# 20260908.net
KiCad netlist of a schematic drawn in Altium Designer
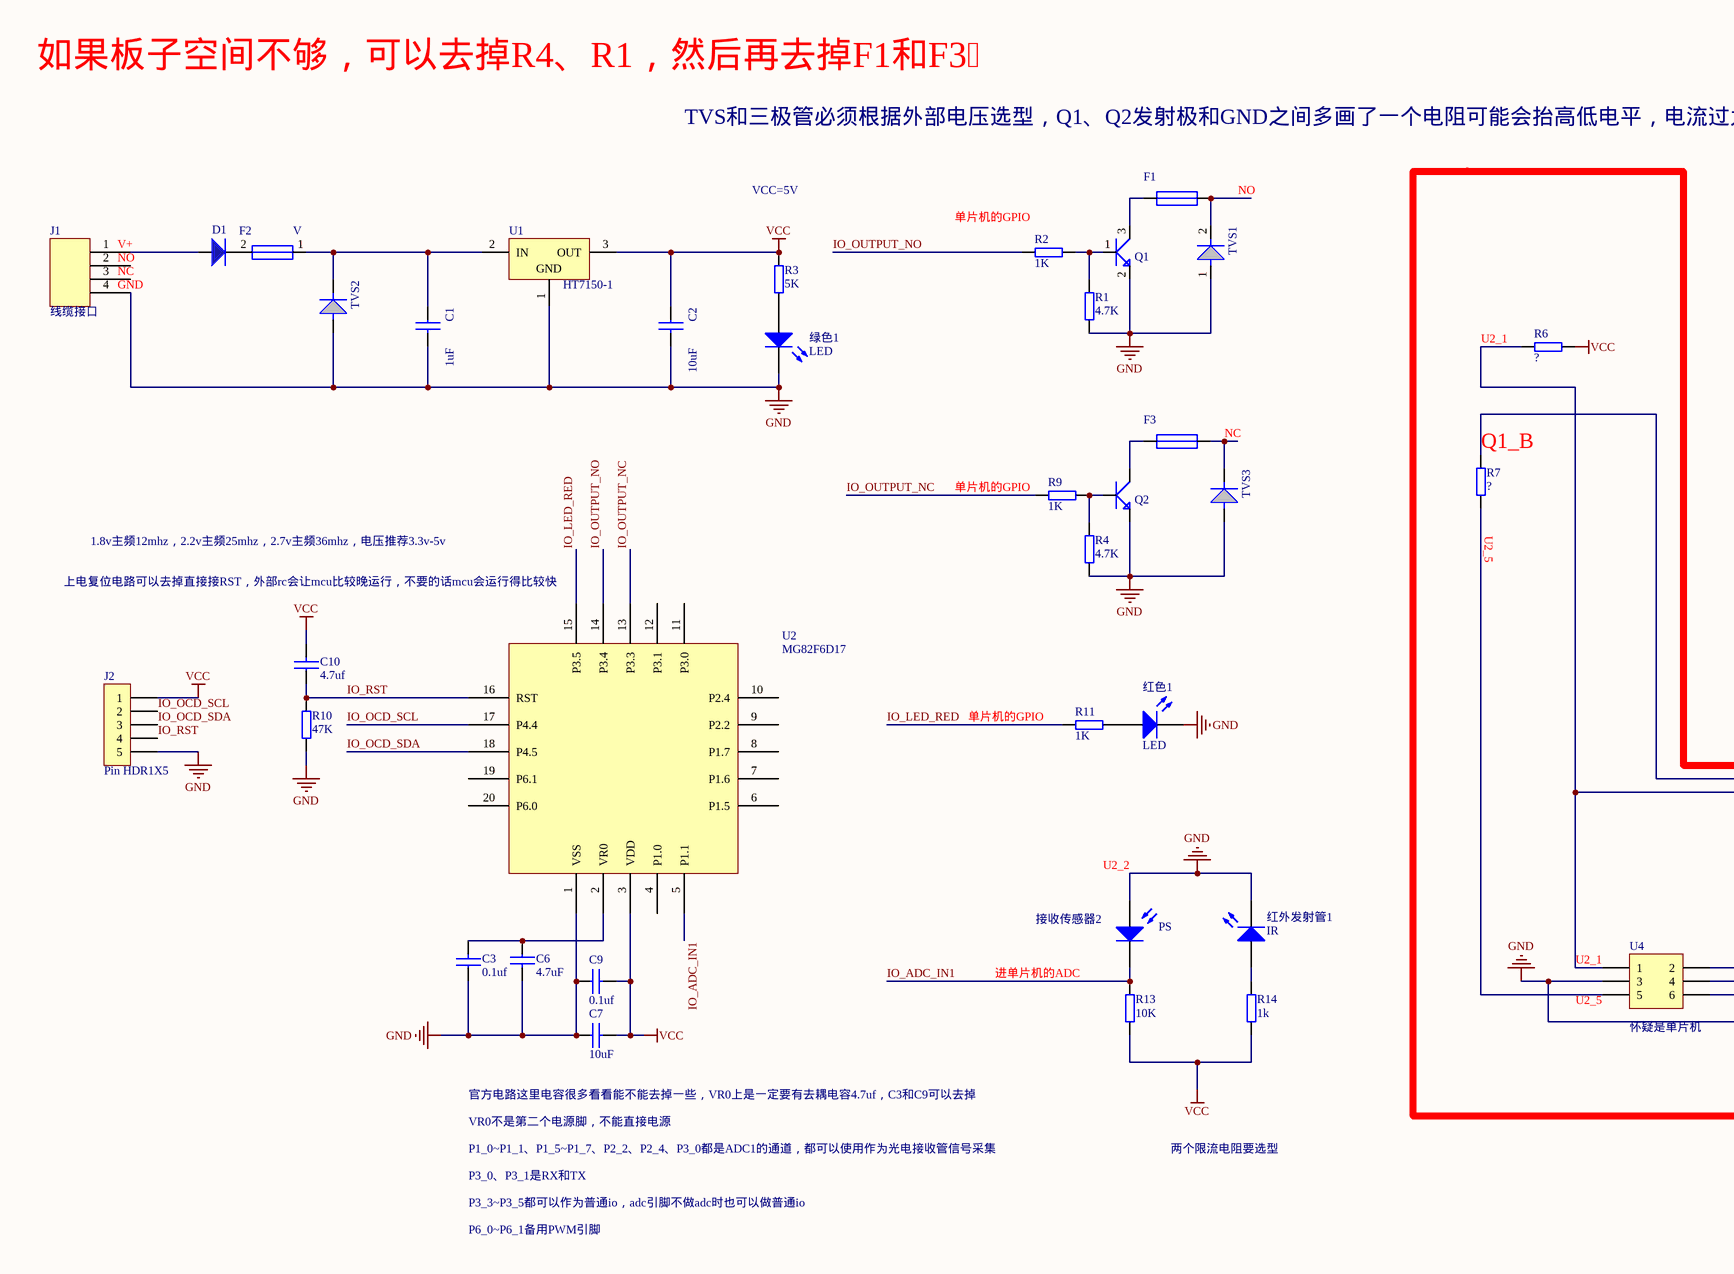
[diagram p0: 槽形开关原理图20260908.SchDoc, left]
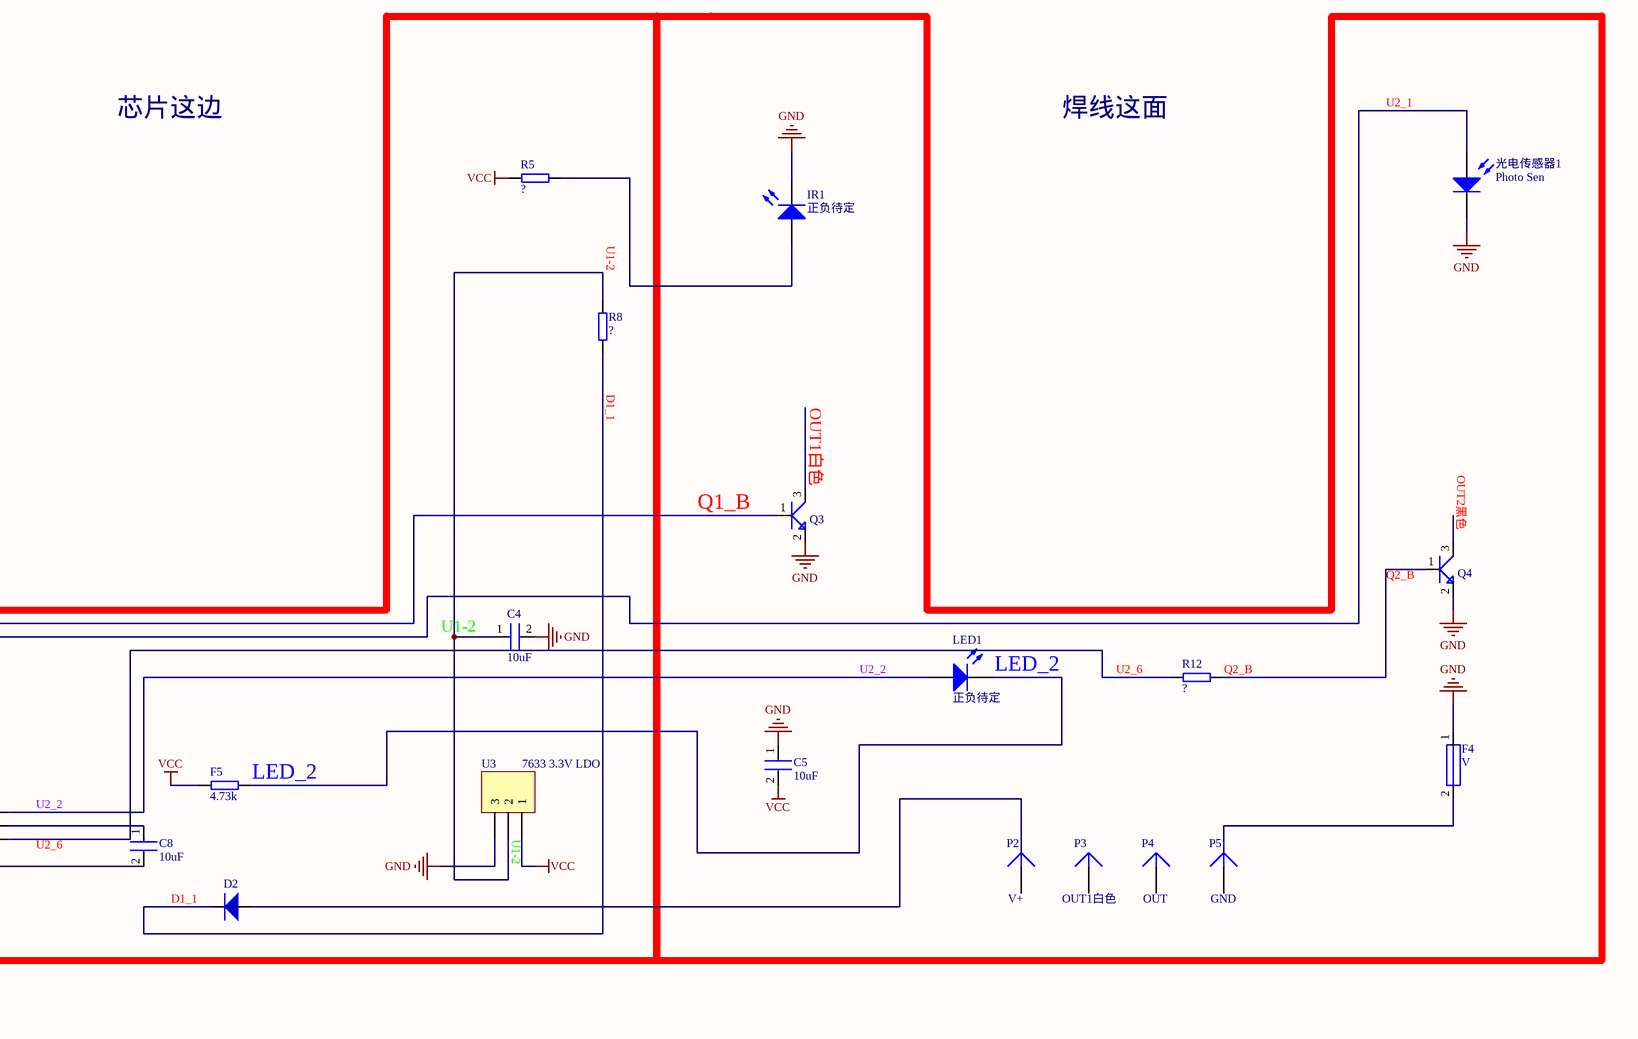
[diagram p1: 槽形开关原理图20260908.SchDoc, right]

(export (version "E")
  (design (tool "Eeschema 10.0.6"))
  (components
    (comp (ref "C1") (value "1uF") (footprint "1206") (libsource (lib "*") (part "CAP NP")))
    (comp (ref "C2") (value "10uF") (footprint "1206") (libsource (lib "*") (part "CAP NP")))
    (comp (ref "C3") (value "0.1uf") (footprint "1206") (libsource (lib "*") (part "CAP NP")))
    (comp (ref "C4") (value "10uF") (libsource (lib "*") (part "CAP")))
    (comp (ref "C5") (value "10uF") (libsource (lib "*") (part "CAP")))
    (comp (ref "C6") (value "4.7uF") (footprint "1206") (libsource (lib "*") (part "CAP NP")))
    (comp (ref "C7") (value "10uF") (footprint "1206") (libsource (lib "*") (part "CAP NP")))
    (comp (ref "C8") (value "10uF") (libsource (lib "*") (part "CAP")))
    (comp (ref "C9") (value "0.1uf") (footprint "1206") (libsource (lib "*") (part "CAP NP")))
    (comp (ref "C10") (value "4.7uf") (footprint "1206") (libsource (lib "*") (part "CAP NP")))
    (comp (ref "D1") (value "~") (libsource (lib "*") (part "D")))
    (comp (ref "D2") (value "~") (libsource (lib "*") (part "D")))
    (comp (ref "F1") (value "V") (footprint "0805") (libsource (lib "") (part "FUSE_0_2")))
    (comp (ref "F2") (value "V") (footprint "0805") (libsource (lib "*") (part "FUSE_0")))
    (comp (ref "F3") (value "~") (footprint "0805") (libsource (lib "") (part "FUSE_0_2")))
    (comp (ref "F4") (value "V") (footprint "0805") (libsource (lib "") (part "FUSE_0_1")))
    (comp (ref "F5") (value "4.73k") (libsource (lib "*") (part "RES")))
    (comp (ref "IR1")
      (value "正负待定")
      (footprint "LED-0")
      (description "Typical INFRARED GaAs LED")
      (fields (field (name "PUBLISHER") "Altium Limited"))
      (libsource (lib "Miscellaneous Devices") (part "LED0"))
    )
    (comp (ref "J1") (value "线缆接口") (footprint "SIP4") (libsource (lib "*") (part "4H")))
    (comp (ref "J2")
      (value "Pin HDR1X5")
      (footprint "Pin HDR1X5/2mm-W")
      (libsource (lib "排针") (part "Pin HDR1X5"))
    )
    (comp (ref "LED1")
      (value "正负待定")
      (footprint "LED-0")
      (description "Typical INFRARED GaAs LED")
      (fields (field (name "PUBLISHER") "Altium Limited"))
      (libsource (lib "Miscellaneous Devices") (part "LED0"))
    )
    (comp (ref "P2")
      (value "V+")
      (footprint "PIN1")
      (description "Plug")
      (fields (field (name "PUBLISHER") "Altium Limited"))
      (libsource (lib "Miscellaneous Connectors") (part "Plug"))
    )
    (comp (ref "P3")
      (value "OUT1白色")
      (footprint "PIN1")
      (description "Plug")
      (fields (field (name "PUBLISHER") "Altium Limited"))
      (libsource (lib "Miscellaneous Connectors") (part "Plug"))
    )
    (comp (ref "P4")
      (value "OUT")
      (footprint "PIN1")
      (description "Plug")
      (fields (field (name "PUBLISHER") "Altium Limited"))
      (libsource (lib "Miscellaneous Connectors") (part "Plug"))
    )
    (comp (ref "P5")
      (value "GND")
      (footprint "PIN1")
      (description "Plug")
      (fields (field (name "PUBLISHER") "Altium Limited"))
      (libsource (lib "Miscellaneous Connectors") (part "Plug"))
    )
    (comp (ref "Q1") (value "2SC4617TLR") (libsource (lib "*") (part "2SC4617")))
    (comp (ref "Q2") (value "2SC4617TLR") (libsource (lib "") (part "2SC4617_1")))
    (comp (ref "Q3") (value "2SC4617TLR") (libsource (lib "*") (part "2SC4617")))
    (comp (ref "Q4") (value "2SC4617TLR") (libsource (lib "*") (part "2SC4617")))
    (comp (ref "R1") (value "4.7K") (libsource (lib "*") (part "RES")))
    (comp (ref "R2") (value "1K") (libsource (lib "*") (part "RES")))
    (comp (ref "R3") (value "5K") (libsource (lib "*") (part "RES")))
    (comp (ref "R4") (value "4.7K") (libsource (lib "*") (part "RES")))
    (comp (ref "R5") (value "?") (libsource (lib "*") (part "RES")))
    (comp (ref "R6") (value "?") (libsource (lib "*") (part "RES")))
    (comp (ref "R7") (value "?") (libsource (lib "*") (part "RES")))
    (comp (ref "R8") (value "?") (libsource (lib "*") (part "RES")))
    (comp (ref "R9") (value "1K") (libsource (lib "*") (part "RES")))
    (comp (ref "R10") (value "47K") (libsource (lib "*") (part "RES")))
    (comp (ref "R11") (value "1K") (libsource (lib "*") (part "RES")))
    (comp (ref "R12") (value "?") (libsource (lib "*") (part "RES")))
    (comp (ref "R13") (value "10K") (libsource (lib "*") (part "RES")))
    (comp (ref "R14") (value "1k") (libsource (lib "*") (part "RES")))
    (comp (ref "TVS1") (value "~") (footprint "1206") (libsource (lib "") (part "D1N3063_0_1")))
    (comp (ref "TVS2") (value "M1") (footprint "1206") (libsource (lib "*") (part "D1N3063_0")))
    (comp (ref "TVS3") (value "~") (footprint "1206") (libsource (lib "*") (part "D1N3063_0")))
    (comp (ref "U1")
      (value "HT7150-1")
      (footprint "SOT89N")
      (description "3.0V 100mA Low Power,  Low Dropout Voltage (LDO) Regulator")
      (fields (field (name "PUBLISHER") "Altium Limited"))
      (libsource (lib "Holtek Power Mgt Voltage Regulator") (part "HT7530-1"))
    )
    (comp (ref "U2") (value "MG82F6D17") (libsource (lib "wwrDevice") (part "MG82F6D17 QFN20")))
    (comp (ref "U3")
      (value "7633 3.3V LDO")
      (footprint "HDR1X3")
      (description "Header, 3-Pin")
      (fields (field (name "PUBLISHER") "Altium Limited"))
      (libsource (lib "Miscellaneous Connectors") (part "Header 3"))
    )
    (comp (ref "U4")
      (value "怀疑是单片机")
      (footprint "HDR2X3")
      (description "Header, 3-Pin, Dual row")
      (fields (field (name "PUBLISHER") "Altium Limited"))
      (libsource (lib "Miscellaneous Connectors") (part "Header 3X2"))
    )
    (comp (ref "光电传感器1")
      (value "Photo Sen")
      (footprint "PIN2")
      (description "Photosensitive Diode")
      (fields (field (name "PUBLISHER") "Altium Limited"))
      (libsource (lib "Miscellaneous Devices") (part "Photo Sen"))
    )
    (comp (ref "接收传感器2")
      (value "PS")
      (footprint "PIN2")
      (description "Photosensitive Diode")
      (fields (field (name "PUBLISHER") "Altium Limited"))
      (libsource (lib "Miscellaneous Devices") (part "Photo Sen"))
    )
    (comp (ref "红外发射管1")
      (value "IR")
      (footprint "LED-0")
      (description "Typical INFRARED GaAs LED")
      (fields (field (name "PUBLISHER") "Altium Limited"))
      (libsource (lib "Miscellaneous Devices") (part "LED0"))
    )
    (comp (ref "红色1")
      (value "LED")
      (footprint "LED-0")
      (description "Typical INFRARED GaAs LED")
      (fields (field (name "PUBLISHER") "Altium Limited"))
      (libsource (lib "Miscellaneous Devices") (part "LED0"))
    )
    (comp (ref "绿色1")
      (value "LED")
      (footprint "LED-0")
      (description "Typical INFRARED GaAs LED")
      (fields (field (name "PUBLISHER") "Altium Limited"))
      (libsource (lib "Miscellaneous Devices") (part "LED0"))
    )
  )
  (nets
    (net (code "1") (name "/IO_ADC_IN1") (class "Default")
      (node (ref "R13") (pin "2") (pinfunction "2_2") (pintype "passive"))
      (node (ref "U2") (pin "5") (pinfunction "P1.1_5") (pintype "passive"))
      (node (ref "接收传感器2") (pin "2") (pinfunction "K_2") (pintype "passive"))
    )
    (net (code "2") (name "/IO_LED_RED") (class "Default")
      (node (ref "R11") (pin "1") (pinfunction "1_1") (pintype "passive"))
      (node (ref "U2") (pin "15") (pinfunction "P3.5_15") (pintype "passive"))
    )
    (net (code "3") (name "/IO_OCD_SCL") (class "Default")
      (node (ref "J2") (pin "2") (pinfunction "2_2") (pintype "passive"))
      (node (ref "U2") (pin "17") (pinfunction "P4.4_17") (pintype "passive"))
    )
    (net (code "4") (name "/IO_OCD_SDA") (class "Default")
      (node (ref "J2") (pin "3") (pinfunction "3_3") (pintype "passive"))
      (node (ref "U2") (pin "18") (pinfunction "P4.5_18") (pintype "passive"))
    )
    (net (code "5") (name "/IO_OUTPUT_NC") (class "Default")
      (node (ref "R9") (pin "1") (pinfunction "1_1") (pintype "passive"))
      (node (ref "U2") (pin "13") (pinfunction "P3.3_13") (pintype "passive"))
    )
    (net (code "6") (name "/IO_OUTPUT_NO") (class "Default")
      (node (ref "R2") (pin "1") (pinfunction "1_1") (pintype "passive"))
      (node (ref "U2") (pin "14") (pinfunction "P3.4_14") (pintype "passive"))
    )
    (net (code "7") (name "/IO_RST") (class "Default")
      (node (ref "C10") (pin "1") (pinfunction "1_1") (pintype "passive"))
      (node (ref "J2") (pin "4") (pinfunction "4_4") (pintype "passive"))
      (node (ref "R10") (pin "2") (pinfunction "2_2") (pintype "passive"))
      (node (ref "U2") (pin "16") (pinfunction "RST_16") (pintype "passive"))
    )
    (net (code "8") (name "GND") (class "Default")
      (node (ref "C1") (pin "2") (pinfunction "2_2") (pintype "passive"))
      (node (ref "C2") (pin "2") (pinfunction "2_2") (pintype "passive"))
      (node (ref "C3") (pin "1") (pinfunction "1_1") (pintype "passive"))
      (node (ref "C4") (pin "2") (pintype "passive"))
      (node (ref "C5") (pin "1") (pintype "passive"))
      (node (ref "C6") (pin "2") (pinfunction "2_2") (pintype "passive"))
      (node (ref "C7") (pin "1") (pinfunction "1_1") (pintype "passive"))
      (node (ref "C8") (pin "2") (pintype "passive"))
      (node (ref "C9") (pin "1") (pinfunction "1_1") (pintype "passive"))
      (node (ref "F4") (pin "1") (pinfunction "1_1") (pintype "passive"))
      (node (ref "IR1") (pin "2") (pinfunction "K_2") (pintype "passive"))
      (node (ref "J1") (pin "4") (pintype "passive"))
      (node (ref "J2") (pin "5") (pinfunction "5_5") (pintype "passive"))
      (node (ref "Q1") (pin "2") (pinfunction "E_2") (pintype "passive"))
      (node (ref "Q2") (pin "2") (pinfunction "E_2") (pintype "passive"))
      (node (ref "Q3") (pin "2") (pinfunction "E_2") (pintype "passive"))
      (node (ref "Q4") (pin "2") (pinfunction "E_2") (pintype "passive"))
      (node (ref "R1") (pin "2") (pinfunction "2_2") (pintype "passive"))
      (node (ref "R10") (pin "1") (pinfunction "1_1") (pintype "passive"))
      (node (ref "R4") (pin "2") (pinfunction "2_2") (pintype "passive"))
      (node (ref "TVS1") (pin "1") (pinfunction "1_1") (pintype "passive"))
      (node (ref "TVS2") (pin "1") (pinfunction "1_1") (pintype "passive"))
      (node (ref "TVS3") (pin "1") (pinfunction "1_1") (pintype "passive"))
      (node (ref "U1") (pin "1") (pinfunction "GND_1") (pintype "power_in"))
      (node (ref "U2") (pin "1") (pinfunction "VSS_1") (pintype "passive"))
      (node (ref "U3") (pin "3") (pinfunction "3_3") (pintype "passive"))
      (node (ref "U4") (pin "3") (pinfunction "3_3") (pintype "passive"))
      (node (ref "光电传感器1") (pin "2") (pinfunction "K_2") (pintype "passive"))
      (node (ref "接收传感器2") (pin "1") (pinfunction "A_1") (pintype "passive"))
      (node (ref "红外发射管1") (pin "2") (pinfunction "K_2") (pintype "passive"))
      (node (ref "红色1") (pin "2") (pinfunction "K_2") (pintype "passive"))
      (node (ref "绿色1") (pin "2") (pinfunction "K_2") (pintype "passive"))
    )
    (net (code "9") (name "Net-(C4-Pad1)") (class "Default")
      (node (ref "C4") (pin "1") (pintype "passive"))
      (node (ref "R8") (pin "2") (pinfunction "2_2") (pintype "passive"))
      (node (ref "U3") (pin "2") (pinfunction "2_2") (pintype "passive"))
    )
    (net (code "10") (name "Net-(C8-Pad1)") (class "Default")
      (node (ref "C8") (pin "1") (pintype "passive"))
      (node (ref "U4") (pin "4") (pinfunction "4_4") (pintype "passive"))
    )
    (net (code "11") (name "Net-(D1-Pad1)") (class "Default")
      (node (ref "D1") (pin "1") (pintype "passive"))
      (node (ref "J1") (pin "1") (pintype "passive"))
    )
    (net (code "12") (name "Net-(D1-Pad2)") (class "Default")
      (node (ref "D1") (pin "2") (pintype "passive"))
      (node (ref "F2") (pin "2") (pinfunction "2_2") (pintype "passive"))
    )
    (net (code "13") (name "Net-(D2-Pad2)") (class "Default")
      (node (ref "D2") (pin "2") (pintype "passive"))
      (node (ref "R8") (pin "1") (pinfunction "1_1") (pintype "passive"))
    )
    (net (code "14") (name "Net-(F1-Pad1)") (class "Default")
      (node (ref "F1") (pin "1") (pinfunction "1_1") (pintype "passive"))
      (node (ref "TVS1") (pin "2") (pinfunction "2_2") (pintype "passive"))
    )
    (net (code "15") (name "Net-(F3-Pad1)") (class "Default")
      (node (ref "F3") (pin "1") (pinfunction "1_1") (pintype "passive"))
      (node (ref "TVS3") (pin "2") (pinfunction "2_2") (pintype "passive"))
    )
    (net (code "16") (name "Net-(IR1-A)") (class "Default")
      (node (ref "IR1") (pin "1") (pinfunction "A_1") (pintype "passive"))
      (node (ref "R5") (pin "1") (pinfunction "1_1") (pintype "passive"))
    )
    (net (code "17") (name "Net-(LED1-A)") (class "Default")
      (node (ref "LED1") (pin "1") (pinfunction "A_1") (pintype "passive"))
      (node (ref "U4") (pin "2") (pinfunction "2_2") (pintype "passive"))
    )
    (net (code "18") (name "Net-(LED1-K)") (class "Default")
      (node (ref "F5") (pin "1") (pinfunction "1_1") (pintype "passive"))
      (node (ref "LED1") (pin "2") (pinfunction "K_2") (pintype "passive"))
    )
    (net (code "19") (name "Net-(Q1-B)") (class "Default")
      (node (ref "Q1") (pin "1") (pinfunction "B_1") (pintype "passive"))
      (node (ref "R1") (pin "1") (pinfunction "1_1") (pintype "passive"))
      (node (ref "R2") (pin "2") (pinfunction "2_2") (pintype "passive"))
    )
    (net (code "20") (name "Net-(Q1-C)") (class "Default")
      (node (ref "F1") (pin "2") (pinfunction "2_2") (pintype "passive"))
      (node (ref "Q1") (pin "3") (pinfunction "C_3") (pintype "passive"))
    )
    (net (code "21") (name "Net-(Q2-B)") (class "Default")
      (node (ref "Q2") (pin "1") (pinfunction "B_1") (pintype "passive"))
      (node (ref "R4") (pin "1") (pinfunction "1_1") (pintype "passive"))
      (node (ref "R9") (pin "2") (pinfunction "2_2") (pintype "passive"))
    )
    (net (code "22") (name "Net-(Q2-C)") (class "Default")
      (node (ref "F3") (pin "2") (pinfunction "2_2") (pintype "passive"))
      (node (ref "Q2") (pin "3") (pinfunction "C_3") (pintype "passive"))
    )
    (net (code "23") (name "Net-(Q3-B)") (class "Default")
      (node (ref "Q3") (pin "1") (pinfunction "B_1") (pintype "passive"))
      (node (ref "R7") (pin "2") (pinfunction "2_2") (pintype "passive"))
    )
    (net (code "24") (name "Net-(Q4-B)") (class "Default")
      (node (ref "Q4") (pin "1") (pinfunction "B_1") (pintype "passive"))
      (node (ref "R12") (pin "1") (pinfunction "1_1") (pintype "passive"))
    )
    (net (code "25") (name "Net-(R7-Pad1)") (class "Default")
      (node (ref "R7") (pin "1") (pinfunction "1_1") (pintype "passive"))
      (node (ref "U4") (pin "5") (pinfunction "5_5") (pintype "passive"))
    )
    (net (code "26") (name "Net-(R12-Pad2)") (class "Default")
      (node (ref "R12") (pin "2") (pinfunction "2_2") (pintype "passive"))
      (node (ref "U4") (pin "6") (pinfunction "6_6") (pintype "passive"))
    )
    (net (code "27") (name "Net-(U1-IN)") (class "Default")
      (node (ref "C1") (pin "1") (pinfunction "1_1") (pintype "passive"))
      (node (ref "F2") (pin "1") (pinfunction "1_1") (pintype "passive"))
      (node (ref "TVS2") (pin "2") (pinfunction "2_2") (pintype "passive"))
      (node (ref "U1") (pin "2") (pinfunction "IN_2") (pintype "power_in"))
    )
    (net (code "28") (name "Net-(U2-VR0)") (class "Default")
      (node (ref "C3") (pin "2") (pinfunction "2_2") (pintype "passive"))
      (node (ref "C6") (pin "1") (pinfunction "1_1") (pintype "passive"))
      (node (ref "U2") (pin "2") (pinfunction "VR0_2") (pintype "passive"))
    )
    (net (code "29") (name "Net-(光电传感器1-A)") (class "Default")
      (node (ref "R6") (pin "2") (pinfunction "2_2") (pintype "passive"))
      (node (ref "U4") (pin "1") (pinfunction "1_1") (pintype "passive"))
      (node (ref "光电传感器1") (pin "1") (pinfunction "A_1") (pintype "passive"))
    )
    (net (code "30") (name "Net-(红外发射管1-A)") (class "Default")
      (node (ref "R14") (pin "2") (pinfunction "2_2") (pintype "passive"))
      (node (ref "红外发射管1") (pin "1") (pinfunction "A_1") (pintype "passive"))
    )
    (net (code "31") (name "Net-(红色1-A)") (class "Default")
      (node (ref "R11") (pin "2") (pinfunction "2_2") (pintype "passive"))
      (node (ref "红色1") (pin "1") (pinfunction "A_1") (pintype "passive"))
    )
    (net (code "32") (name "Net-(绿色1-A)") (class "Default")
      (node (ref "R3") (pin "2") (pinfunction "2_2") (pintype "passive"))
      (node (ref "绿色1") (pin "1") (pinfunction "A_1") (pintype "passive"))
    )
    (net (code "33") (name "VCC") (class "Default")
      (node (ref "C10") (pin "2") (pinfunction "2_2") (pintype "passive"))
      (node (ref "C2") (pin "1") (pinfunction "1_1") (pintype "passive"))
      (node (ref "C5") (pin "2") (pintype "passive"))
      (node (ref "C7") (pin "2") (pinfunction "2_2") (pintype "passive"))
      (node (ref "C9") (pin "2") (pinfunction "2_2") (pintype "passive"))
      (node (ref "F5") (pin "2") (pinfunction "2_2") (pintype "passive"))
      (node (ref "J2") (pin "1") (pinfunction "1_1") (pintype "passive"))
      (node (ref "R13") (pin "1") (pinfunction "1_1") (pintype "passive"))
      (node (ref "R14") (pin "1") (pinfunction "1_1") (pintype "passive"))
      (node (ref "R3") (pin "1") (pinfunction "1_1") (pintype "passive"))
      (node (ref "R5") (pin "2") (pinfunction "2_2") (pintype "passive"))
      (node (ref "R6") (pin "1") (pinfunction "1_1") (pintype "passive"))
      (node (ref "U1") (pin "3") (pinfunction "OUT_3") (pintype "power_in"))
      (node (ref "U2") (pin "3") (pinfunction "VDD_3") (pintype "passive"))
      (node (ref "U3") (pin "1") (pinfunction "1_1") (pintype "passive"))
    )
    (net (code "34") (name "unconnected-(D2-Pad1)") (class "Default")
      (node (ref "D2") (pin "1") (pintype "passive"))
    )
    (net (code "35") (name "unconnected-(F4-Pad2)") (class "Default")
      (node (ref "F4") (pin "2") (pinfunction "2_2") (pintype "passive"))
    )
    (net (code "36") (name "unconnected-(J1-Pad2)") (class "Default")
      (node (ref "J1") (pin "2") (pintype "passive"))
    )
    (net (code "37") (name "unconnected-(J1-Pad3)") (class "Default")
      (node (ref "J1") (pin "3") (pintype "passive"))
    )
    (net (code "38") (name "unconnected-(P2-Pad1)") (class "Default")
      (node (ref "P2") (pin "1") (pinfunction "1_1") (pintype "passive"))
    )
    (net (code "39") (name "unconnected-(P3-Pad1)") (class "Default")
      (node (ref "P3") (pin "1") (pinfunction "1_1") (pintype "passive"))
    )
    (net (code "40") (name "unconnected-(P4-Pad1)") (class "Default")
      (node (ref "P4") (pin "1") (pinfunction "1_1") (pintype "passive"))
    )
    (net (code "41") (name "unconnected-(P5-Pad1)") (class "Default")
      (node (ref "P5") (pin "1") (pinfunction "1_1") (pintype "passive"))
    )
    (net (code "42") (name "unconnected-(Q3-C-Pad3)") (class "Default")
      (node (ref "Q3") (pin "3") (pinfunction "C_3") (pintype "passive"))
    )
    (net (code "43") (name "unconnected-(Q4-C-Pad3)") (class "Default")
      (node (ref "Q4") (pin "3") (pinfunction "C_3") (pintype "passive"))
    )
    (net (code "44") (name "unconnected-(U2-P1.0-Pad4)") (class "Default")
      (node (ref "U2") (pin "4") (pinfunction "P1.0_4") (pintype "passive"))
    )
    (net (code "45") (name "unconnected-(U2-P1.5-Pad6)") (class "Default")
      (node (ref "U2") (pin "6") (pinfunction "P1.5_6") (pintype "passive"))
    )
    (net (code "46") (name "unconnected-(U2-P1.6-Pad7)") (class "Default")
      (node (ref "U2") (pin "7") (pinfunction "P1.6_7") (pintype "passive"))
    )
    (net (code "47") (name "unconnected-(U2-P1.7-Pad8)") (class "Default")
      (node (ref "U2") (pin "8") (pinfunction "P1.7_8") (pintype "passive"))
    )
    (net (code "48") (name "unconnected-(U2-P2.2-Pad9)") (class "Default")
      (node (ref "U2") (pin "9") (pinfunction "P2.2_9") (pintype "passive"))
    )
    (net (code "49") (name "unconnected-(U2-P2.4-Pad10)") (class "Default")
      (node (ref "U2") (pin "10") (pinfunction "P2.4_10") (pintype "passive"))
    )
    (net (code "50") (name "unconnected-(U2-P3.0-Pad11)") (class "Default")
      (node (ref "U2") (pin "11") (pinfunction "P3.0_11") (pintype "passive"))
    )
    (net (code "51") (name "unconnected-(U2-P3.1-Pad12)") (class "Default")
      (node (ref "U2") (pin "12") (pinfunction "P3.1_12") (pintype "passive"))
    )
    (net (code "52") (name "unconnected-(U2-P6.0-Pad20)") (class "Default")
      (node (ref "U2") (pin "20") (pinfunction "P6.0_20") (pintype "passive"))
    )
    (net (code "53") (name "unconnected-(U2-P6.1-Pad19)") (class "Default")
      (node (ref "U2") (pin "19") (pinfunction "P6.1_19") (pintype "passive"))
    )
  )
)
